# SignalConditioning.net
KiCad netlist of a schematic drawn in Altium Designer
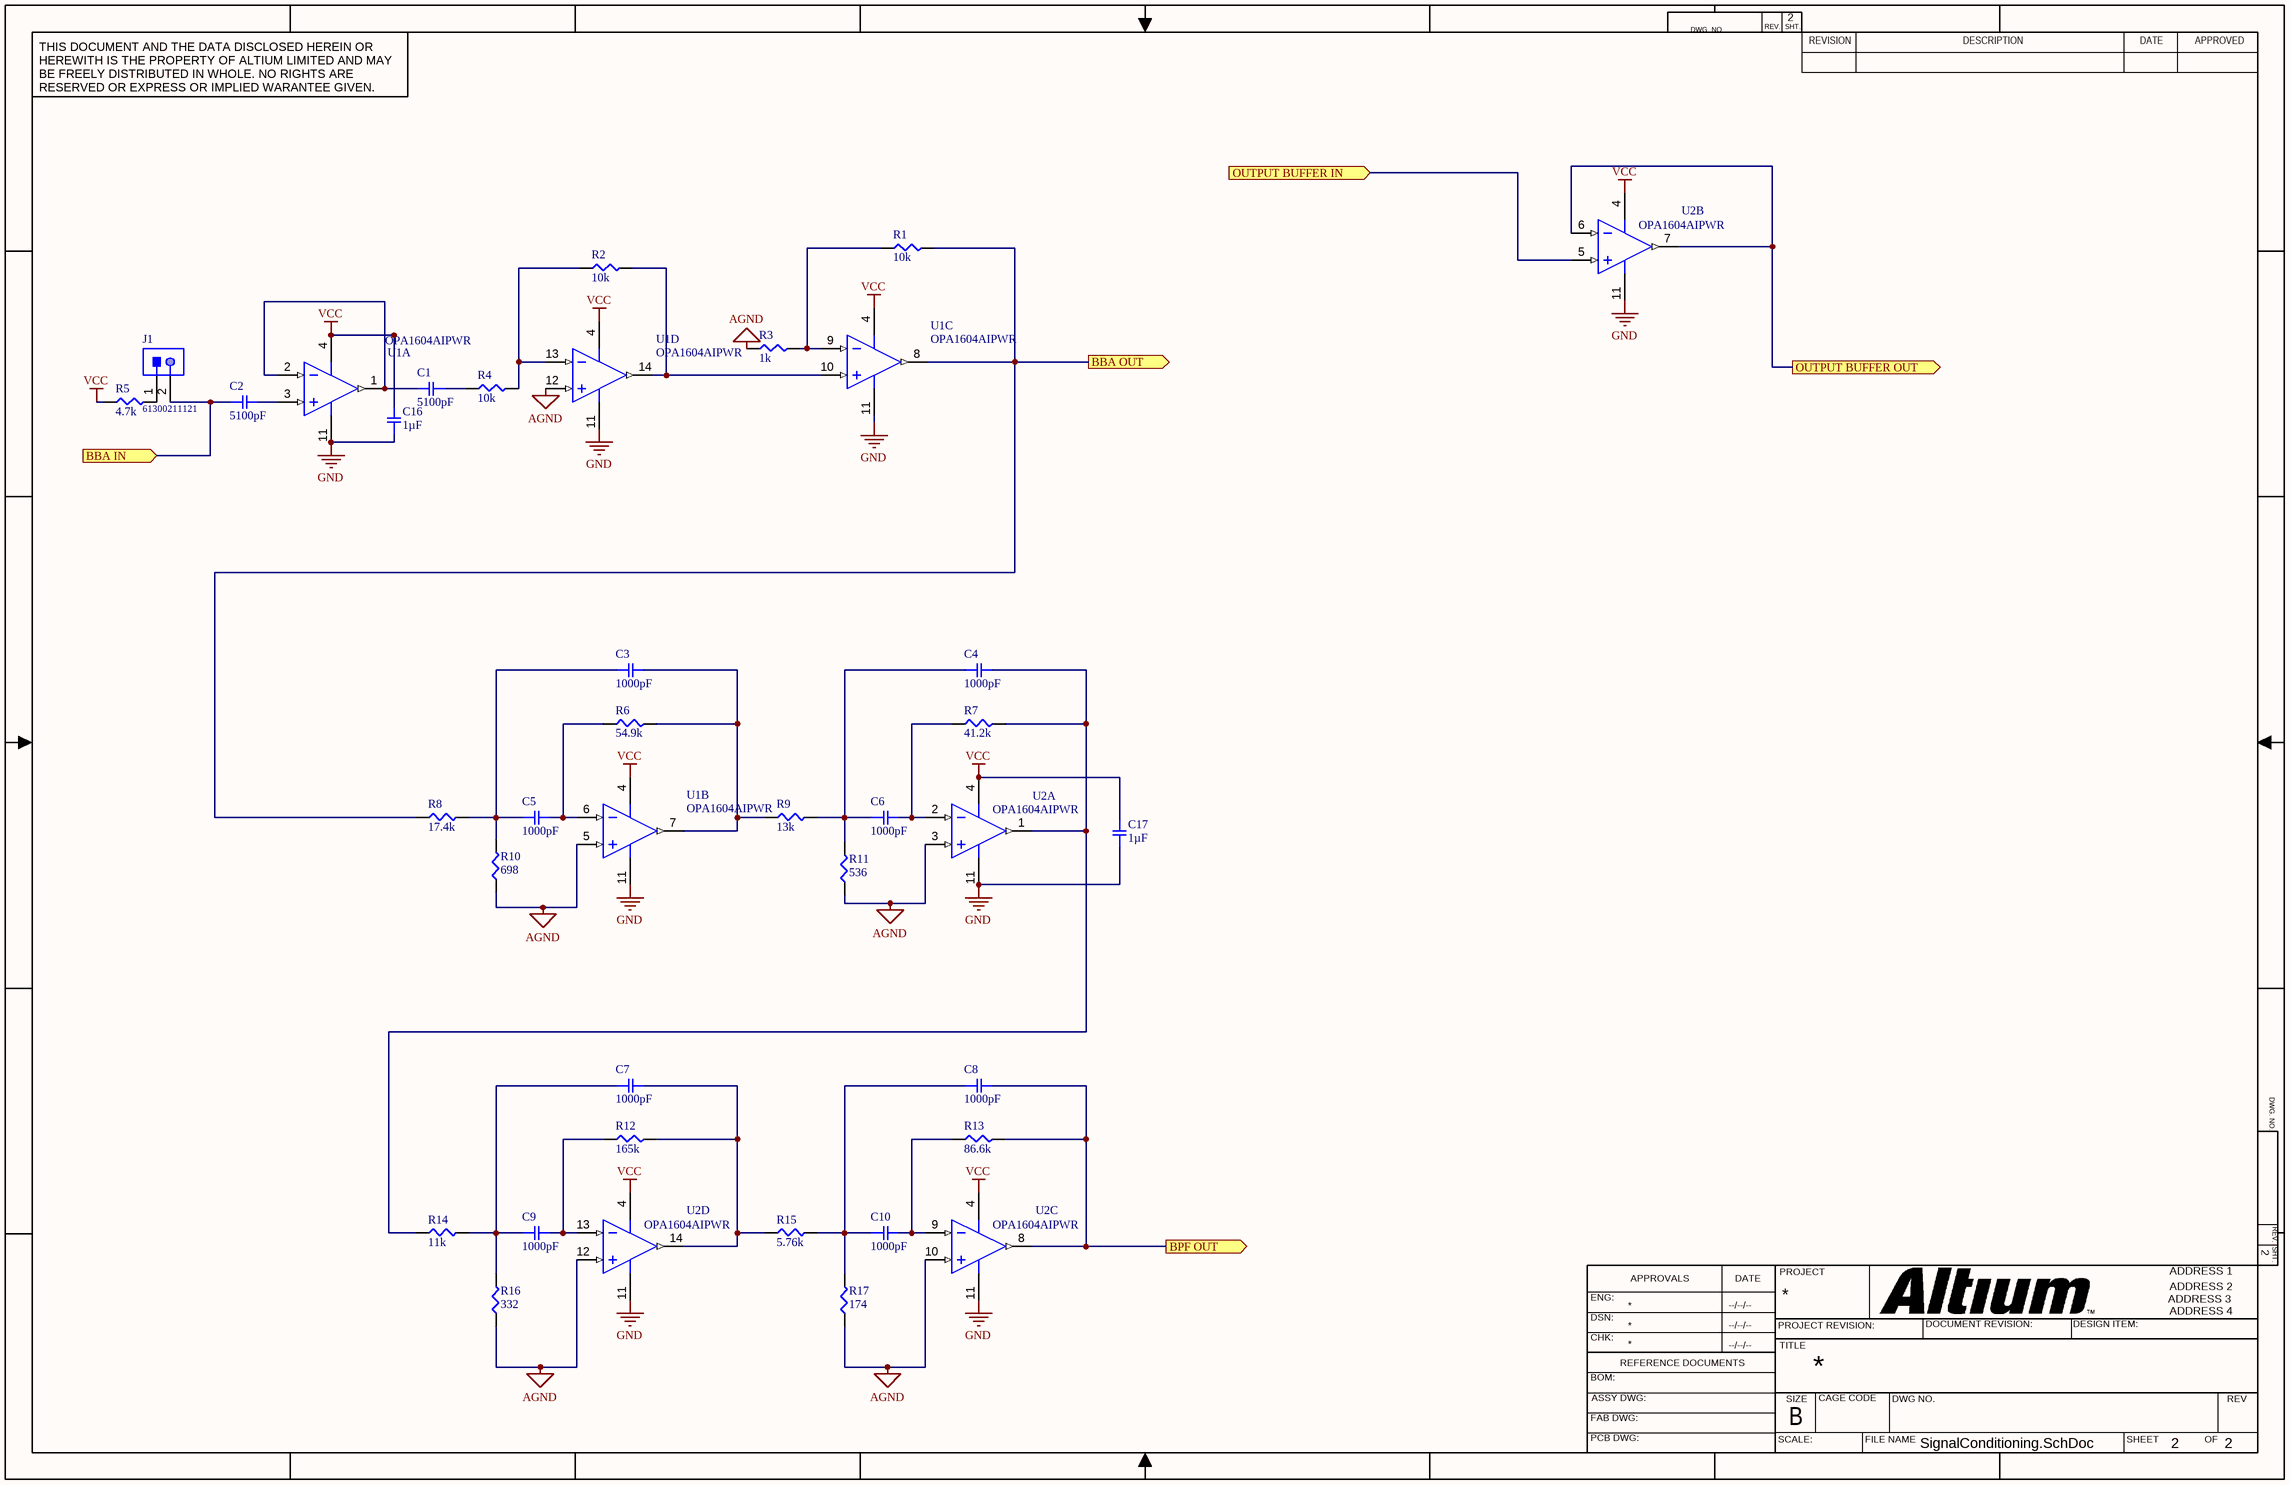
[diagram p0: SignalConditioning.SchDoc]

(export (version "E")
  (design (tool "Eeschema 10.0.6"))
  (components
    (comp (ref "C1")
      (value "5100pF")
      (footprint "SMD-0603C")
      (description "CAP CER 5100PF 50V U2J 0603")
      (fields
        (field (name "MANUFACTURER") "Murata Electronics North America")
        (field (name "MANUFACTURER PART NUMBER") "GRM1887U1H512JA01D")
      )
      (libsource (lib "capacitor_murata_0603") (part "GRM1887U1H512JA01D"))
    )
    (comp (ref "C2")
      (value "5100pF")
      (footprint "SMD-0603C")
      (description "CAP CER 5100PF 50V U2J 0603")
      (fields
        (field (name "DIGI-KEY PART NUMBER") "490-6399-1-ND")
        (field (name "PART NUMBER") "GRM1887U1H512JA01D")
      )
      (libsource (lib "capacitor_murata_0603") (part "GRM1887U1H512JA01D"))
    )
    (comp (ref "C3")
      (value "1000pF")
      (footprint "SMD-0603C")
      (description "CAP CER 1000PF 50V X7R 0603")
      (fields
        (field (name "MANUFACTURER") "Walsin Technology Corporation")
        (field (name "MANUFACTURER PART NUMBER") "0603N102F500CT")
      )
      (libsource (lib "capacitor_murata_0603") (part "GCJ188R71H102KA01D"))
    )
    (comp (ref "C4")
      (value "1000pF")
      (footprint "SMD-0603C")
      (description "CAP CER 1000PF 50V X7R 0603")
      (fields
        (field (name "MANUFACTURER") "Walsin Technology Corporation")
        (field (name "MANUFACTURER PART NUMBER") "0603N102F500CT")
      )
      (libsource (lib "capacitor_murata_0603") (part "GCJ188R71H102KA01D"))
    )
    (comp (ref "C5")
      (value "1000pF")
      (footprint "SMD-0603C")
      (description "CAP CER 1000PF 50V X7R 0603")
      (fields
        (field (name "MANUFACTURER") "Walsin Technology Corporation")
        (field (name "MANUFACTURER PART NUMBER") "0603N102F500CT")
      )
      (libsource (lib "capacitor_murata_0603") (part "GCJ188R71H102KA01D"))
    )
    (comp (ref "C6")
      (value "1000pF")
      (footprint "SMD-0603C")
      (description "CAP CER 1000PF 50V X7R 0603")
      (fields
        (field (name "MANUFACTURER") "Walsin Technology Corporation")
        (field (name "MANUFACTURER PART NUMBER") "0603N102F500CT")
      )
      (libsource (lib "capacitor_murata_0603") (part "GCJ188R71H102KA01D"))
    )
    (comp (ref "C7")
      (value "1000pF")
      (footprint "SMD-0603C")
      (description "CAP CER 1000PF 50V X7R 0603")
      (fields
        (field (name "MANUFACTURER") "Walsin Technology Corporation")
        (field (name "MANUFACTURER PART NUMBER") "0603N102F500CT")
      )
      (libsource (lib "capacitor_murata_0603") (part "GCJ188R71H102KA01D"))
    )
    (comp (ref "C8")
      (value "1000pF")
      (footprint "SMD-0603C")
      (description "CAP CER 1000PF 50V X7R 0603")
      (fields
        (field (name "MANUFACTURER") "Walsin Technology Corporation")
        (field (name "MANUFACTURER PART NUMBER") "0603N102F500CT")
      )
      (libsource (lib "capacitor_murata_0603") (part "GCJ188R71H102KA01D"))
    )
    (comp (ref "C9")
      (value "1000pF")
      (footprint "SMD-0603C")
      (description "CAP CER 1000PF 50V X7R 0603")
      (fields
        (field (name "MANUFACTURER") "Walsin Technology Corporation")
        (field (name "MANUFACTURER PART NUMBER") "0603N102F500CT")
      )
      (libsource (lib "capacitor_murata_0603") (part "GCJ188R71H102KA01D"))
    )
    (comp (ref "C10")
      (value "1000pF")
      (footprint "SMD-0603C")
      (description "CAP CER 1000PF 50V X7R 0603")
      (fields
        (field (name "MANUFACTURER") "Walsin Technology Corporation")
        (field (name "MANUFACTURER PART NUMBER") "0603N102F500CT")
      )
      (libsource (lib "capacitor_murata_0603") (part "GCJ188R71H102KA01D"))
    )
    (comp (ref "C16")
      (value "1µF")
      (footprint "SMD-0603C")
      (description "CAP CER 1UF 16V X7R 0603")
      (fields
        (field (name "MANUFACTURER") "Samsung Electro-Mechanics")
        (field (name "MANUFACTURER PART NUMBER") "CL10A105KA8NNNC")
      )
      (libsource (lib "capacitor_murata_0603") (part "GCM188R71C105KA64D"))
    )
    (comp (ref "C17")
      (value "1µF")
      (footprint "SMD-0603C")
      (description "CAP CER 1UF 16V X7R 0603")
      (fields
        (field (name "MANUFACTURER") "Samsung Electro-Mechanics")
        (field (name "MANUFACTURER PART NUMBER") "CL10A105KA8NNNC")
      )
      (libsource (lib "capacitor_murata_0603") (part "GCM188R71C105KA64D"))
    )
    (comp (ref "J1")
      (value "61300211121")
      (footprint "61300211121")
      (description "THT Vertical Pin Header WR-PHD, Pitch 2.54 mm, Single Row, 2 pins")
      (fields (field (name "MANUFACTURER") "Wurth Elektronik") (field (name "PUBLISHER") "WurthElektronik"))
      (libsource (lib "Altium Content Vault") (part "WE-CN-1P-M-R2"))
    )
    (comp (ref "R1")
      (value "10k")
      (footprint "SMD-0603-RES")
      (description "RES SMD 10K OHM 1% 1/10W 0603")
      (fields
        (field (name "MANUFACTURER") "Panasonic Electronic Components")
        (field (name "MANUFACTURER PART NUMBER") "RNCP0603FTD10K0")
      )
      (libsource (lib "Panasonic_resistor_0603") (part "ERJ-3EKF1002V"))
    )
    (comp (ref "R2")
      (value "10k")
      (footprint "SMD-0603-RES")
      (description "RES SMD 10K OHM 1% 1/10W 0603")
      (fields
        (field (name "MANUFACTURER") "Panasonic Electronic Components")
        (field (name "MANUFACTURER PART NUMBER") "RNCP0603FTD10K0")
      )
      (libsource (lib "Panasonic_resistor_0603") (part "ERJ-3EKF1002V"))
    )
    (comp (ref "R3")
      (value "1k")
      (footprint "SMD-0603-RES")
      (description "RES SMD 1K OHM 1% 1/10W 0603")
      (fields
        (field (name "MANUFACTURER") "Stackpole Electronics Inc")
        (field (name "MANUFACTURER PART NUMBER") "RNCP0603FTD1K00")
      )
      (libsource (lib "Panasonic_resistor_0603") (part "ERJ-3EKF1001V"))
    )
    (comp (ref "R4")
      (value "10k")
      (footprint "SMD-0603-RES")
      (description "RES SMD 10K OHM 1% 1/10W 0603")
      (fields
        (field (name "MANUFACTURER") "Panasonic Electronic Components")
        (field (name "MANUFACTURER PART NUMBER") "RNCP0603FTD10K0")
      )
      (libsource (lib "Panasonic_resistor_0603") (part "ERJ-3EKF1002V"))
    )
    (comp (ref "R5")
      (value "4.7k")
      (footprint "SMD-0603-RES")
      (description "RES SMD 4.7K OHM 1% 1/10W 0603")
      (fields
        (field (name "MANUFACTURER") "Panasonic Electronic Components")
        (field (name "MANUFACTURER PART NUMBER") "ERJ-3EKF4701V")
      )
      (libsource (lib "Panasonic_resistor_0603") (part "ERJ-3EKF4701V"))
    )
    (comp (ref "R6")
      (value "54.9k")
      (footprint "SMD-0603-RES")
      (description "RES SMD 54.9K OHM 1% 1/10W 0603")
      (fields
        (field (name "MANUFACTURER") "Panasonic Electronic Components")
        (field (name "MANUFACTURER PART NUMBER") "ERJ-3EKF5492V")
      )
      (libsource (lib "Panasonic_resistor_0603") (part "ERJ-3EKF5492V"))
    )
    (comp (ref "R7")
      (value "41.2k")
      (footprint "SMD-0603-RES")
      (description "RES SMD 41.2K OHM 1% 1/10W 0603")
      (fields
        (field (name "MANUFACTURER") "Panasonic Electronic Components")
        (field (name "MANUFACTURER PART NUMBER") "ERJ-3EKF4122V")
      )
      (libsource (lib "Panasonic_resistor_0603") (part "ERJ-3EKF4122V"))
    )
    (comp (ref "R8")
      (value "17.4k")
      (footprint "SMD-0603-RES")
      (description "RES SMD 17.4K OHM 1% 1/10W 0603")
      (fields
        (field (name "MANUFACTURER") "Panasonic Electronic Components")
        (field (name "MANUFACTURER PART NUMBER") "ERJ-3EKF1742V")
      )
      (libsource (lib "Panasonic_resistor_0603") (part "ERJ-3EKF1742V"))
    )
    (comp (ref "R9")
      (value "13k")
      (footprint "SMD-0603-RES")
      (description "RES SMD 13K OHM 1% 1/10W 0603")
      (fields
        (field (name "MANUFACTURER") "Panasonic Electronic Components")
        (field (name "MANUFACTURER PART NUMBER") "ERJ-3EKF1302V")
      )
      (libsource (lib "Panasonic_resistor_0603") (part "ERJ-3EKF1302V"))
    )
    (comp (ref "R10")
      (value "698")
      (footprint "SMD-0603-RES")
      (description "RES SMD 698 OHM 1% 1/10W 0603")
      (fields
        (field (name "MANUFACTURER") "Panasonic Electronic Components")
        (field (name "MANUFACTURER PART NUMBER") "ERJ-3EKF6980V")
      )
      (libsource (lib "Panasonic_resistor_0603") (part "ERJ-3EKF6980V"))
    )
    (comp (ref "R11")
      (value "536")
      (footprint "SMD-0603-RES")
      (description "RES SMD 536 OHM 1% 1/10W 0603")
      (fields
        (field (name "MANUFACTURER") "Panasonic Electronic Components")
        (field (name "MANUFACTURER PART NUMBER") "ERJ-3EKF5360V")
      )
      (libsource (lib "Panasonic_resistor_0603") (part "ERJ-3EKF5360V"))
    )
    (comp (ref "R12")
      (value "165k")
      (footprint "SMD-0603-RES")
      (description "RES SMD 165K OHM 1% 1/10W 0603")
      (fields
        (field (name "MANUFACTURER") "Panasonic Electronic Components")
        (field (name "MANUFACTURER PART NUMBER") "ERJ-3EKF1653V")
      )
      (libsource (lib "Panasonic_resistor_0603") (part "ERJ-3EKF1653V"))
    )
    (comp (ref "R13")
      (value "86.6k")
      (footprint "SMD-0603-RES")
      (description "RES SMD 86.6K OHM 1% 1/10W 0603")
      (fields
        (field (name "MANUFACTURER") "Panasonic Electronic Components")
        (field (name "MANUFACTURER PART NUMBER") "ERJ-3EKF8662V")
      )
      (libsource (lib "Panasonic_resistor_0603") (part "ERJ-3EKF8662V"))
    )
    (comp (ref "R14")
      (value "11k")
      (footprint "SMD-0603-RES")
      (description "RES SMD 11K OHM 1% 1/10W 0603")
      (fields
        (field (name "MANUFACTURER") "Panasonic Electronic Components")
        (field (name "MANUFACTURER PART NUMBER") "ERJ-3EKF1102V")
      )
      (libsource (lib "Panasonic_resistor_0603") (part "ERJ-3EKF1102V"))
    )
    (comp (ref "R15")
      (value "5.76k")
      (footprint "SMD-0603-RES")
      (description "RES SMD 5.76K OHM 1% 1/10W 0603")
      (fields
        (field (name "MANUFACTURER") "Panasonic Electronic Components")
        (field (name "MANUFACTURER PART NUMBER") "ERJ-3EKF5761V")
      )
      (libsource (lib "Panasonic_resistor_0603") (part "ERJ-3EKF5761V"))
    )
    (comp (ref "R16")
      (value "332")
      (footprint "SMD-0603-RES")
      (description "RES SMD 332 OHM 1% 1/10W 0603")
      (fields
        (field (name "MANUFACTURER") "Panasonic Electronic Components")
        (field (name "MANUFACTURER PART NUMBER") "ERJ-3EKF3320V")
      )
      (libsource (lib "Panasonic_resistor_0603") (part "ERJ-3EKF3320V"))
    )
    (comp (ref "R17")
      (value "174")
      (footprint "SMD-0603-RES")
      (description "RES SMD 174 OHM 1% 1/10W 0603")
      (fields
        (field (name "MANUFACTURER") "Panasonic Electronic Components")
        (field (name "MANUFACTURER PART NUMBER") "ERJ-3EKF1740V")
      )
      (libsource (lib "Panasonic_resistor_0603") (part "ERJ-3EKF1740V"))
    )
    (comp (ref "U1")
      (value "OPA1604AIPWR")
      (footprint "PW0014A_N")
      (fields (field (name "MANUFACTURER") "Texas Instruments"))
      (libsource (lib "Altium Content Vault") (part "TI-OPA16X4_4XXX-14"))
    )
    (comp (ref "U2")
      (value "OPA1604AIPWR")
      (footprint "PW0014A_N")
      (fields (field (name "MANUFACTURER") "Texas Instruments"))
      (libsource (lib "Altium Content Vault") (part "TI-OPA16X4_4XXX-14"))
    )
  )
  (nets
    (net (code "1") (name "/BBA IN") (class "Default")
      (node (ref "C2") (pin "1") (pinfunction "1_1") (pintype "passive"))
      (node (ref "J1") (pin "2") (pinfunction "2_2") (pintype "passive"))
    )
    (net (code "2") (name "/BBA OUT") (class "Default")
      (node (ref "R1") (pin "2") (pinfunction "2_2") (pintype "passive"))
      (node (ref "R8") (pin "1") (pinfunction "1_1") (pintype "passive"))
      (node (ref "U1") (pin "8") (pinfunction "OUT_C_8") (pintype "output"))
    )
    (net (code "3") (name "/BPF OUT") (class "Default")
      (node (ref "C8") (pin "2") (pinfunction "2_2") (pintype "passive"))
      (node (ref "R13") (pin "2") (pinfunction "2_2") (pintype "passive"))
      (node (ref "U2") (pin "8") (pinfunction "OUT_C_8") (pintype "output"))
    )
    (net (code "4") (name "/OUTPUT BUFFER IN") (class "Default")
      (node (ref "U2") (pin "5") (pinfunction "IN_B+_5") (pintype "input"))
    )
    (net (code "5") (name "/OUTPUT BUFFER OUT") (class "Default")
      (node (ref "U2") (pin "6") (pinfunction "IN_B-_6") (pintype "input"))
      (node (ref "U2") (pin "7") (pinfunction "OUT_B_7") (pintype "output"))
    )
    (net (code "6") (name "AGND") (class "Default")
      (node (ref "R10") (pin "1") (pinfunction "1_1") (pintype "passive"))
      (node (ref "R11") (pin "1") (pinfunction "1_1") (pintype "passive"))
      (node (ref "R16") (pin "1") (pinfunction "1_1") (pintype "passive"))
      (node (ref "R17") (pin "1") (pinfunction "1_1") (pintype "passive"))
      (node (ref "R3") (pin "1") (pinfunction "1_1") (pintype "passive"))
      (node (ref "U1") (pin "12") (pinfunction "IN_D+_12") (pintype "input"))
      (node (ref "U1") (pin "5") (pinfunction "IN_B+_5") (pintype "input"))
      (node (ref "U2") (pin "10") (pinfunction "IN_C+_10") (pintype "input"))
      (node (ref "U2") (pin "12") (pinfunction "IN_D+_12") (pintype "input"))
      (node (ref "U2") (pin "3") (pinfunction "IN_A+_3") (pintype "input"))
    )
    (net (code "7") (name "GND") (class "Default")
      (node (ref "C16") (pin "1") (pinfunction "1_1") (pintype "passive"))
      (node (ref "C17") (pin "1") (pinfunction "1_1") (pintype "passive"))
      (node (ref "U1") (pin "11") (pinfunction "V-_11") (pintype "power_in"))
      (node (ref "U2") (pin "11") (pinfunction "V-_11") (pintype "power_in"))
    )
    (net (code "8") (name "Net-(C1-Pad1)") (class "Default")
      (node (ref "C1") (pin "1") (pinfunction "1_1") (pintype "passive"))
      (node (ref "R4") (pin "1") (pinfunction "1_1") (pintype "passive"))
    )
    (net (code "9") (name "Net-(C3-Pad1)") (class "Default")
      (node (ref "C3") (pin "1") (pinfunction "1_1") (pintype "passive"))
      (node (ref "C5") (pin "1") (pinfunction "1_1") (pintype "passive"))
      (node (ref "R10") (pin "2") (pinfunction "2_2") (pintype "passive"))
      (node (ref "R8") (pin "2") (pinfunction "2_2") (pintype "passive"))
    )
    (net (code "10") (name "Net-(C4-Pad1)") (class "Default")
      (node (ref "C4") (pin "1") (pinfunction "1_1") (pintype "passive"))
      (node (ref "C6") (pin "1") (pinfunction "1_1") (pintype "passive"))
      (node (ref "R11") (pin "2") (pinfunction "2_2") (pintype "passive"))
      (node (ref "R9") (pin "2") (pinfunction "2_2") (pintype "passive"))
    )
    (net (code "11") (name "Net-(C7-Pad1)") (class "Default")
      (node (ref "C7") (pin "1") (pinfunction "1_1") (pintype "passive"))
      (node (ref "C9") (pin "1") (pinfunction "1_1") (pintype "passive"))
      (node (ref "R14") (pin "2") (pinfunction "2_2") (pintype "passive"))
      (node (ref "R16") (pin "2") (pinfunction "2_2") (pintype "passive"))
    )
    (net (code "12") (name "Net-(C10-Pad1)") (class "Default")
      (node (ref "C10") (pin "1") (pinfunction "1_1") (pintype "passive"))
      (node (ref "C8") (pin "1") (pinfunction "1_1") (pintype "passive"))
      (node (ref "R15") (pin "2") (pinfunction "2_2") (pintype "passive"))
      (node (ref "R17") (pin "2") (pinfunction "2_2") (pintype "passive"))
    )
    (net (code "13") (name "Net-(J1-Pad1)") (class "Default")
      (node (ref "J1") (pin "1") (pinfunction "1_1") (pintype "passive"))
      (node (ref "R5") (pin "2") (pinfunction "2_2") (pintype "passive"))
    )
    (net (code "14") (name "Net-(U1A-IN_A+)") (class "Default")
      (node (ref "C2") (pin "2") (pinfunction "2_2") (pintype "passive"))
      (node (ref "U1") (pin "3") (pinfunction "IN_A+_3") (pintype "input"))
    )
    (net (code "15") (name "Net-(U1A-IN_A-)") (class "Default")
      (node (ref "C1") (pin "2") (pinfunction "2_2") (pintype "passive"))
      (node (ref "U1") (pin "1") (pinfunction "OUT_A_1") (pintype "output"))
      (node (ref "U1") (pin "2") (pinfunction "IN_A-_2") (pintype "input"))
    )
    (net (code "16") (name "Net-(U1B-IN_B-)") (class "Default")
      (node (ref "C5") (pin "2") (pinfunction "2_2") (pintype "passive"))
      (node (ref "R6") (pin "1") (pinfunction "1_1") (pintype "passive"))
      (node (ref "U1") (pin "6") (pinfunction "IN_B-_6") (pintype "input"))
    )
    (net (code "17") (name "Net-(U1B-OUT_B)") (class "Default")
      (node (ref "C3") (pin "2") (pinfunction "2_2") (pintype "passive"))
      (node (ref "R6") (pin "2") (pinfunction "2_2") (pintype "passive"))
      (node (ref "R9") (pin "1") (pinfunction "1_1") (pintype "passive"))
      (node (ref "U1") (pin "7") (pinfunction "OUT_B_7") (pintype "output"))
    )
    (net (code "18") (name "Net-(U1C-IN_C+)") (class "Default")
      (node (ref "R2") (pin "2") (pinfunction "2_2") (pintype "passive"))
      (node (ref "U1") (pin "10") (pinfunction "IN_C+_10") (pintype "input"))
      (node (ref "U1") (pin "14") (pinfunction "OUT_D_14") (pintype "output"))
    )
    (net (code "19") (name "Net-(U1C-IN_C-)") (class "Default")
      (node (ref "R1") (pin "1") (pinfunction "1_1") (pintype "passive"))
      (node (ref "R3") (pin "2") (pinfunction "2_2") (pintype "passive"))
      (node (ref "U1") (pin "9") (pinfunction "IN_C-_9") (pintype "input"))
    )
    (net (code "20") (name "Net-(U1D-IN_D-)") (class "Default")
      (node (ref "R2") (pin "1") (pinfunction "1_1") (pintype "passive"))
      (node (ref "R4") (pin "2") (pinfunction "2_2") (pintype "passive"))
      (node (ref "U1") (pin "13") (pinfunction "IN_D-_13") (pintype "input"))
    )
    (net (code "21") (name "Net-(U2A-IN_A-)") (class "Default")
      (node (ref "C6") (pin "2") (pinfunction "2_2") (pintype "passive"))
      (node (ref "R7") (pin "1") (pinfunction "1_1") (pintype "passive"))
      (node (ref "U2") (pin "2") (pinfunction "IN_A-_2") (pintype "input"))
    )
    (net (code "22") (name "Net-(U2A-OUT_A)") (class "Default")
      (node (ref "C4") (pin "2") (pinfunction "2_2") (pintype "passive"))
      (node (ref "R14") (pin "1") (pinfunction "1_1") (pintype "passive"))
      (node (ref "R7") (pin "2") (pinfunction "2_2") (pintype "passive"))
      (node (ref "U2") (pin "1") (pinfunction "OUT_A_1") (pintype "output"))
    )
    (net (code "23") (name "Net-(U2C-IN_C-)") (class "Default")
      (node (ref "C10") (pin "2") (pinfunction "2_2") (pintype "passive"))
      (node (ref "R13") (pin "1") (pinfunction "1_1") (pintype "passive"))
      (node (ref "U2") (pin "9") (pinfunction "IN_C-_9") (pintype "input"))
    )
    (net (code "24") (name "Net-(U2D-IN_D-)") (class "Default")
      (node (ref "C9") (pin "2") (pinfunction "2_2") (pintype "passive"))
      (node (ref "R12") (pin "1") (pinfunction "1_1") (pintype "passive"))
      (node (ref "U2") (pin "13") (pinfunction "IN_D-_13") (pintype "input"))
    )
    (net (code "25") (name "Net-(U2D-OUT_D)") (class "Default")
      (node (ref "C7") (pin "2") (pinfunction "2_2") (pintype "passive"))
      (node (ref "R12") (pin "2") (pinfunction "2_2") (pintype "passive"))
      (node (ref "R15") (pin "1") (pinfunction "1_1") (pintype "passive"))
      (node (ref "U2") (pin "14") (pinfunction "OUT_D_14") (pintype "output"))
    )
    (net (code "26") (name "VCC") (class "Default")
      (node (ref "C16") (pin "2") (pinfunction "2_2") (pintype "passive"))
      (node (ref "C17") (pin "2") (pinfunction "2_2") (pintype "passive"))
      (node (ref "R5") (pin "1") (pinfunction "1_1") (pintype "passive"))
      (node (ref "U1") (pin "4") (pinfunction "V+_4") (pintype "power_in"))
      (node (ref "U2") (pin "4") (pinfunction "V+_4") (pintype "power_in"))
    )
  )
)
